# speech.net
KiCad netlist of a schematic drawn in EAGLE
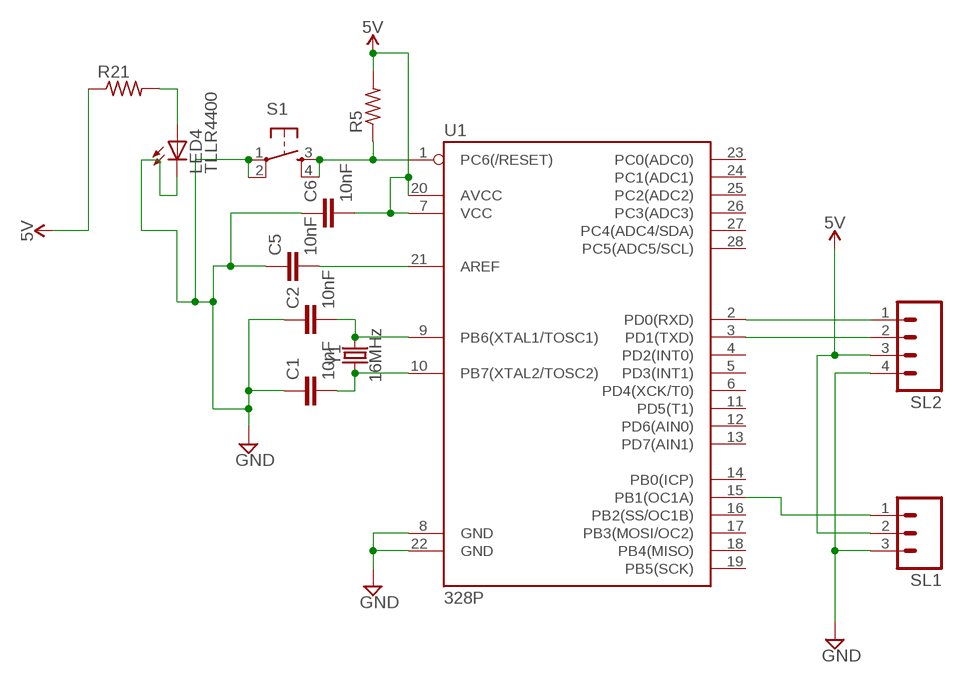
[diagram p0: schematic, sheet 1]

(export (version "E")
  (design (tool "Eeschema 10.0.6"))
  (components
    (comp (ref "C1")
      (value "10nF")
      (footprint "eagle-import:CAP-PTH-10MM")
      (libsource (lib "eagle-import") (part "10NF-PTH-10MM-10000V-1-%"))
    )
    (comp (ref "C2")
      (value "10nF")
      (footprint "eagle-import:CAP-PTH-10MM")
      (libsource (lib "eagle-import") (part "10NF-PTH-10MM-10000V-1-%"))
    )
    (comp (ref "C5")
      (value "10nF")
      (footprint "eagle-import:CAP-PTH-10MM")
      (libsource (lib "eagle-import") (part "10NF-PTH-10MM-10000V-1-%"))
    )
    (comp (ref "C6")
      (value "10nF")
      (footprint "eagle-import:CAP-PTH-10MM")
      (libsource (lib "eagle-import") (part "10NF-PTH-10MM-10000V-1-%"))
    )
    (comp (ref "LED4")
      (value "TLLR4400")
      (footprint "eagle-import:LED3MM")
      (fields (field (name "MF") "VISHAY SEMICONDUCTOR"))
      (libsource (lib "eagle-import") (part "TLLR4400"))
    )
    (comp (ref "R5")
      (value "R-US_0207/12")
      (footprint "eagle-import:0207_12")
      (libsource (lib "eagle-import") (part "R-US_0207/12"))
    )
    (comp (ref "R21")
      (value "R-US_0207/12")
      (footprint "eagle-import:0207_12")
      (libsource (lib "eagle-import") (part "R-US_0207/12"))
    )
    (comp (ref "S1")
      (value "TAC_SWITCHPTH")
      (footprint "eagle-import:TACTILE-PTH")
      (libsource (lib "eagle-import") (part "TAC_SWITCHPTH"))
    )
    (comp (ref "SL1")
      (value "MA03")
      (footprint "eagle-import:03P")
      (libsource (lib "eagle-import") (part "MA03"))
    )
    (comp (ref "SL2")
      (value "MA04")
      (footprint "eagle-import:04PA")
      (libsource (lib "eagle-import") (part "MA04"))
    )
    (comp (ref "U1")
      (value "328P")
      (footprint "eagle-import:DIP28")
      (libsource (lib "eagle-import") (part "ATMEGA328P_PDIP"))
    )
    (comp (ref "Y1")
      (value "16MHz")
      (footprint "eagle-import:HC49US")
      (libsource (lib "eagle-import") (part "CRYSTAL-16MHZPTH-HC49US"))
    )
  )
  (nets
    (net (code "1") (name "5V") (class "Default")
      (node (ref "C6") (pin "2") (pinfunction "2_2") (pintype "passive"))
      (node (ref "R21") (pin "1") (pinfunction "1_1") (pintype "passive"))
      (node (ref "R5") (pin "2") (pinfunction "2_2") (pintype "passive"))
      (node (ref "SL1") (pin "2") (pinfunction "2_2") (pintype "passive"))
      (node (ref "SL2") (pin "3") (pinfunction "3_3") (pintype "passive"))
      (node (ref "U1") (pin "20") (pinfunction "AVCC_20") (pintype "bidirectional"))
      (node (ref "U1") (pin "7") (pinfunction "VCC_7") (pintype "bidirectional"))
    )
    (net (code "2") (name "GND") (class "Default")
      (node (ref "C1") (pin "1") (pinfunction "1_1") (pintype "passive"))
      (node (ref "C2") (pin "1") (pinfunction "1_1") (pintype "passive"))
      (node (ref "C5") (pin "1") (pinfunction "1_1") (pintype "passive"))
      (node (ref "C6") (pin "1") (pinfunction "1_1") (pintype "passive"))
      (node (ref "LED4") (pin "K") (pinfunction "C_K") (pintype "passive"))
      (node (ref "S1") (pin "1") (pinfunction "1_1") (pintype "passive"))
      (node (ref "S1") (pin "2") (pinfunction "2_2") (pintype "passive"))
      (node (ref "SL1") (pin "3") (pinfunction "3_3") (pintype "passive"))
      (node (ref "SL2") (pin "4") (pinfunction "4_4") (pintype "passive"))
      (node (ref "U1") (pin "22") (pinfunction "GND_22") (pintype "bidirectional"))
      (node (ref "U1") (pin "8") (pinfunction "GND_8") (pintype "bidirectional"))
    )
    (net (code "3") (name "Net-(LED4-PadA)") (class "Default")
      (node (ref "LED4") (pin "A") (pinfunction "A_A") (pintype "passive"))
      (node (ref "R21") (pin "2") (pinfunction "2_2") (pintype "passive"))
    )
    (net (code "4") (name "Net-(U1-AREF)") (class "Default")
      (node (ref "C5") (pin "2") (pinfunction "2_2") (pintype "passive"))
      (node (ref "U1") (pin "21") (pinfunction "AREF_21") (pintype "bidirectional"))
    )
    (net (code "5") (name "Net-(U1-PB1(OC1A))") (class "Default")
      (node (ref "SL1") (pin "1") (pinfunction "1_1") (pintype "passive"))
      (node (ref "U1") (pin "15") (pinfunction "PB1(OC1A)_15") (pintype "bidirectional"))
    )
    (net (code "6") (name "Net-(U1-PB6(XTAL1{slash}TOSC1))") (class "Default")
      (node (ref "C2") (pin "2") (pinfunction "2_2") (pintype "passive"))
      (node (ref "U1") (pin "9") (pinfunction "PB6(XTAL1/TOSC1)_9") (pintype "bidirectional"))
      (node (ref "Y1") (pin "2") (pinfunction "2_2") (pintype "passive"))
    )
    (net (code "7") (name "Net-(U1-PB7(XTAL2{slash}TOSC2))") (class "Default")
      (node (ref "C1") (pin "2") (pinfunction "2_2") (pintype "passive"))
      (node (ref "U1") (pin "10") (pinfunction "PB7(XTAL2/TOSC2)_10") (pintype "bidirectional"))
      (node (ref "Y1") (pin "1") (pinfunction "1_1") (pintype "passive"))
    )
    (net (code "8") (name "Net-(U1-PC6({slash}RESET))") (class "Default")
      (node (ref "R5") (pin "1") (pinfunction "1_1") (pintype "passive"))
      (node (ref "S1") (pin "3") (pinfunction "3_3") (pintype "passive"))
      (node (ref "S1") (pin "4") (pinfunction "4_4") (pintype "passive"))
      (node (ref "U1") (pin "1") (pinfunction "PC6(/RESET)_1") (pintype "bidirectional"))
    )
    (net (code "9") (name "Net-(U1-PD0(RXD))") (class "Default")
      (node (ref "SL2") (pin "1") (pinfunction "1_1") (pintype "passive"))
      (node (ref "U1") (pin "2") (pinfunction "PD0(RXD)_2") (pintype "bidirectional"))
    )
    (net (code "10") (name "Net-(U1-PD1(TXD))") (class "Default")
      (node (ref "SL2") (pin "2") (pinfunction "2_2") (pintype "passive"))
      (node (ref "U1") (pin "3") (pinfunction "PD1(TXD)_3") (pintype "bidirectional"))
    )
    (net (code "11") (name "unconnected-(U1-PB0(ICP)-Pad14)") (class "Default")
      (node (ref "U1") (pin "14") (pinfunction "PB0(ICP)_14") (pintype "bidirectional"))
    )
    (net (code "12") (name "unconnected-(U1-PB2(SS{slash}OC1B)-Pad16)") (class "Default")
      (node (ref "U1") (pin "16") (pinfunction "PB2(SS/OC1B)_16") (pintype "bidirectional"))
    )
    (net (code "13") (name "unconnected-(U1-PB3(MOSI{slash}OC2)-Pad17)") (class "Default")
      (node (ref "U1") (pin "17") (pinfunction "PB3(MOSI/OC2)_17") (pintype "bidirectional"))
    )
    (net (code "14") (name "unconnected-(U1-PB4(MISO)-Pad18)") (class "Default")
      (node (ref "U1") (pin "18") (pinfunction "PB4(MISO)_18") (pintype "bidirectional"))
    )
    (net (code "15") (name "unconnected-(U1-PB5(SCK)-Pad19)") (class "Default")
      (node (ref "U1") (pin "19") (pinfunction "PB5(SCK)_19") (pintype "bidirectional"))
    )
    (net (code "16") (name "unconnected-(U1-PC0(ADC0)-Pad23)") (class "Default")
      (node (ref "U1") (pin "23") (pinfunction "PC0(ADC0)_23") (pintype "bidirectional"))
    )
    (net (code "17") (name "unconnected-(U1-PC1(ADC1)-Pad24)") (class "Default")
      (node (ref "U1") (pin "24") (pinfunction "PC1(ADC1)_24") (pintype "bidirectional"))
    )
    (net (code "18") (name "unconnected-(U1-PC2(ADC2)-Pad25)") (class "Default")
      (node (ref "U1") (pin "25") (pinfunction "PC2(ADC2)_25") (pintype "bidirectional"))
    )
    (net (code "19") (name "unconnected-(U1-PC3(ADC3)-Pad26)") (class "Default")
      (node (ref "U1") (pin "26") (pinfunction "PC3(ADC3)_26") (pintype "bidirectional"))
    )
    (net (code "20") (name "unconnected-(U1-PC4(ADC4{slash}SDA)-Pad27)") (class "Default")
      (node (ref "U1") (pin "27") (pinfunction "PC4(ADC4/SDA)_27") (pintype "bidirectional"))
    )
    (net (code "21") (name "unconnected-(U1-PC5(ADC5{slash}SCL)-Pad28)") (class "Default")
      (node (ref "U1") (pin "28") (pinfunction "PC5(ADC5/SCL)_28") (pintype "bidirectional"))
    )
    (net (code "22") (name "unconnected-(U1-PD2(INT0)-Pad4)") (class "Default")
      (node (ref "U1") (pin "4") (pinfunction "PD2(INT0)_4") (pintype "bidirectional"))
    )
    (net (code "23") (name "unconnected-(U1-PD3(INT1)-Pad5)") (class "Default")
      (node (ref "U1") (pin "5") (pinfunction "PD3(INT1)_5") (pintype "bidirectional"))
    )
    (net (code "24") (name "unconnected-(U1-PD4(XCK{slash}T0)-Pad6)") (class "Default")
      (node (ref "U1") (pin "6") (pinfunction "PD4(XCK/T0)_6") (pintype "bidirectional"))
    )
    (net (code "25") (name "unconnected-(U1-PD5(T1)-Pad11)") (class "Default")
      (node (ref "U1") (pin "11") (pinfunction "PD5(T1)_11") (pintype "bidirectional"))
    )
    (net (code "26") (name "unconnected-(U1-PD6(AIN0)-Pad12)") (class "Default")
      (node (ref "U1") (pin "12") (pinfunction "PD6(AIN0)_12") (pintype "bidirectional"))
    )
    (net (code "27") (name "unconnected-(U1-PD7(AIN1)-Pad13)") (class "Default")
      (node (ref "U1") (pin "13") (pinfunction "PD7(AIN1)_13") (pintype "bidirectional"))
    )
  )
)
